# shield_v7.net
KiCad netlist of a schematic drawn in EAGLE
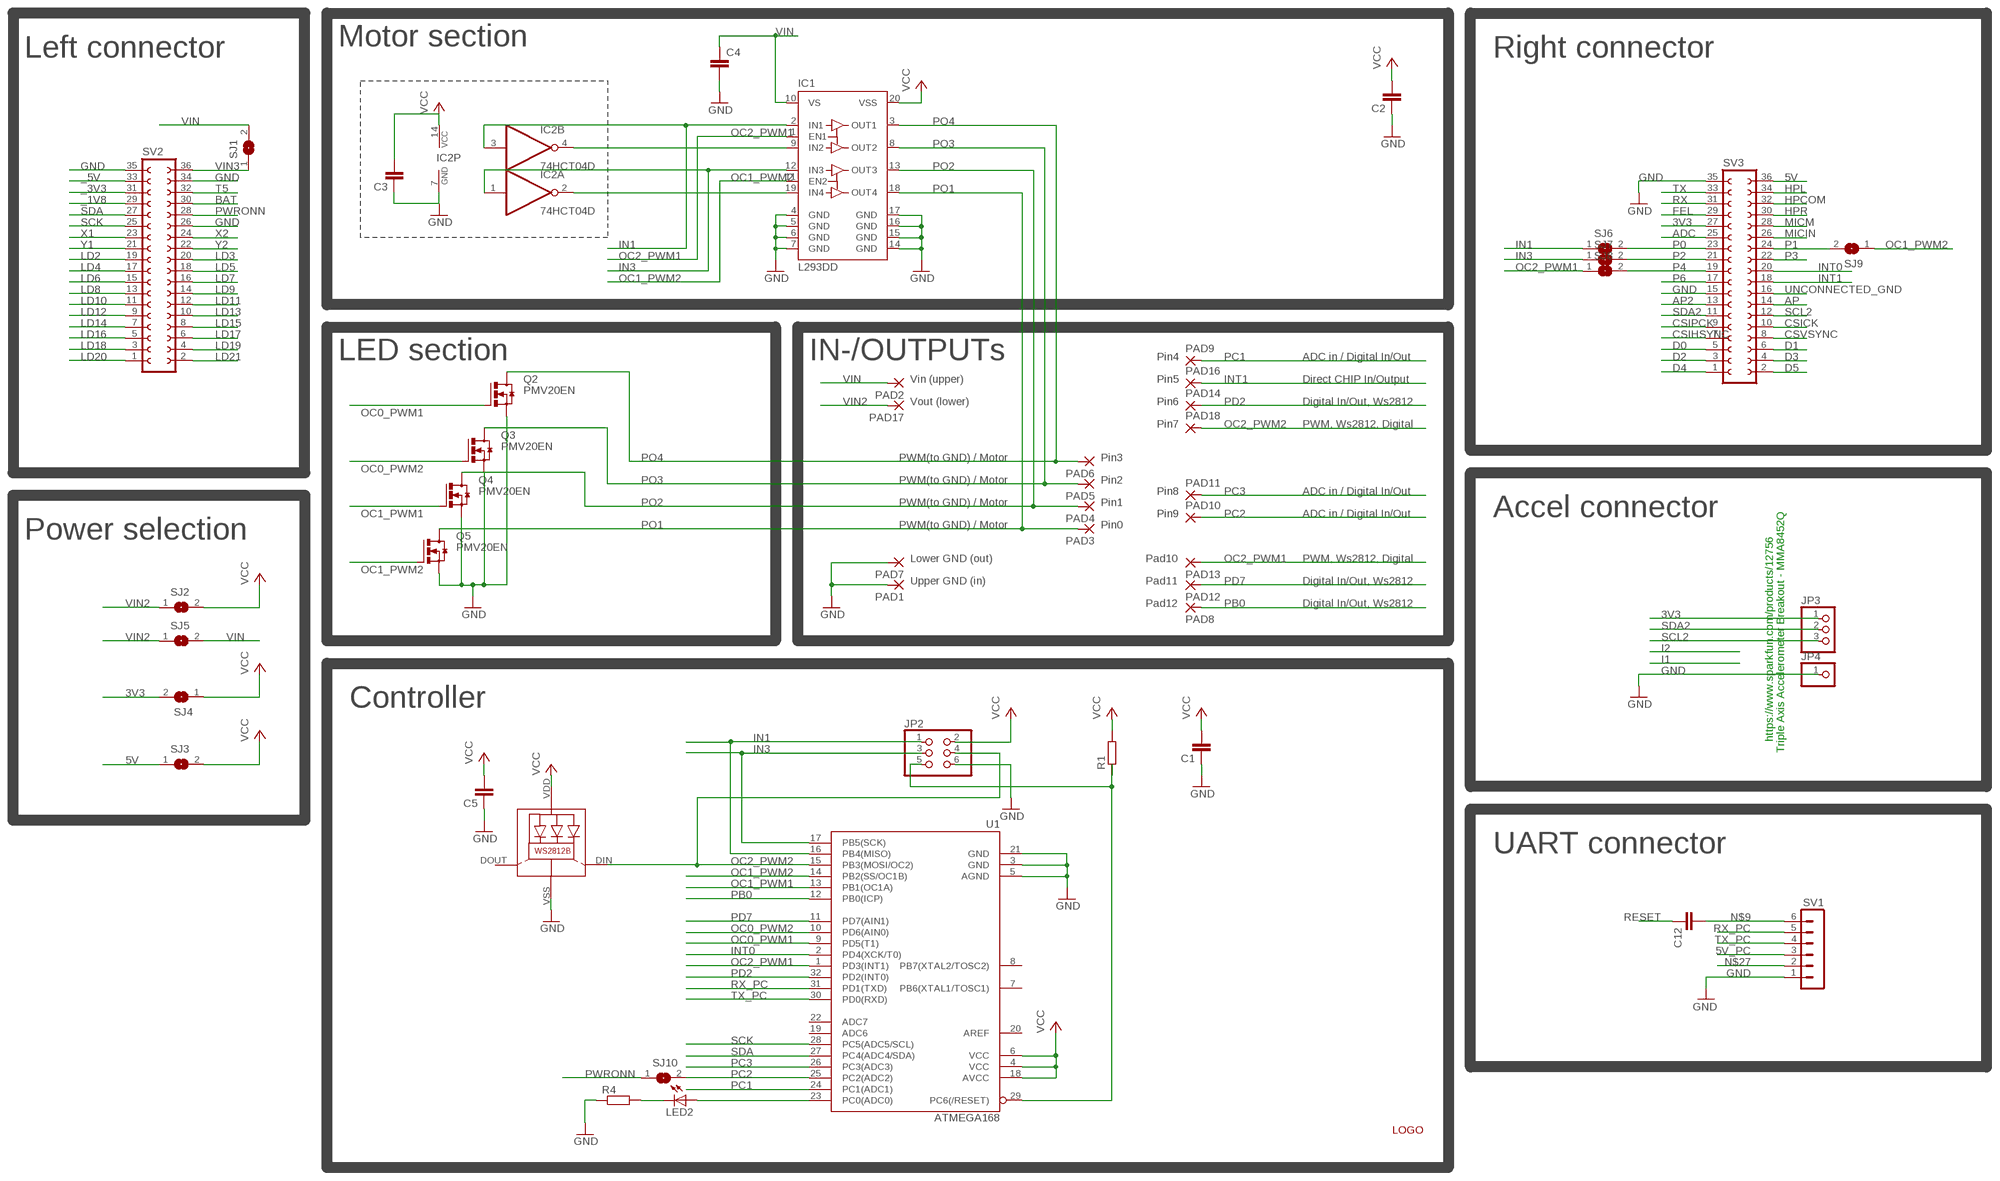
[diagram p0: schematic, sheet 1]

(export (version "E")
  (design (tool "Eeschema 10.0.6"))
  (components
    (comp (ref "C1")
      (value "C-EUC0805")
      (footprint "eagle-import:C0805")
      (libsource (lib "eagle-import") (part "C-EUC0805"))
    )
    (comp (ref "C2")
      (value "C-EUC0805")
      (footprint "eagle-import:C0805")
      (libsource (lib "eagle-import") (part "C-EUC0805"))
    )
    (comp (ref "C3")
      (value "C-EUC0805")
      (footprint "eagle-import:C0805")
      (libsource (lib "eagle-import") (part "C-EUC0805"))
    )
    (comp (ref "C4")
      (value "C-EUC1210")
      (footprint "eagle-import:C1210")
      (libsource (lib "eagle-import") (part "C-EUC1210"))
    )
    (comp (ref "C5")
      (value "C-EUC0805")
      (footprint "eagle-import:C0805")
      (libsource (lib "eagle-import") (part "C-EUC0805"))
    )
    (comp (ref "C12")
      (value "C-EUC1206")
      (footprint "eagle-import:C1206")
      (libsource (lib "eagle-import") (part "C-EUC1206"))
    )
    (comp (ref "IC1")
      (value "L293DD")
      (footprint "eagle-import:SO20")
      (libsource (lib "eagle-import") (part "L293DD"))
    )
    (comp (ref "IC2")
      (value "74HCT04D")
      (footprint "eagle-import:SO14")
      (libsource (lib "eagle-import") (part "7404DHCT"))
    )
    (comp (ref "JP2")
      (value "PINHD-2X3")
      (footprint "eagle-import:2X03")
      (libsource (lib "eagle-import") (part "PINHD-2X3"))
    )
    (comp (ref "JP3")
      (value "PINHD-1X3")
      (footprint "eagle-import:1X03")
      (libsource (lib "eagle-import") (part "PINHD-1X3"))
    )
    (comp (ref "JP4")
      (value "PINHD-1X1")
      (footprint "eagle-import:1X01")
      (libsource (lib "eagle-import") (part "PINHD-1X1"))
    )
    (comp (ref "LED1")
      (value "WS2812B")
      (footprint "eagle-import:WS2812B")
      (libsource (lib "eagle-import") (part "WS2812B"))
    )
    (comp (ref "LED2")
      (value "LEDCHIP-LED0805")
      (footprint "eagle-import:CHIP-LED0805")
      (libsource (lib "eagle-import") (part "LEDCHIP-LED0805"))
    )
    (comp (ref "PAD1")
      (value "3,17/1,3")
      (footprint "eagle-import:3,17_1,3")
      (libsource (lib "eagle-import") (part "3,17/1,3"))
    )
    (comp (ref "PAD2")
      (value "3,17/1,3")
      (footprint "eagle-import:3,17_1,3")
      (libsource (lib "eagle-import") (part "3,17/1,3"))
    )
    (comp (ref "PAD3")
      (value "3,17/1,3")
      (footprint "eagle-import:3,17_1,3")
      (libsource (lib "eagle-import") (part "3,17/1,3"))
    )
    (comp (ref "PAD4")
      (value "3,17/1,3")
      (footprint "eagle-import:3,17_1,3")
      (libsource (lib "eagle-import") (part "3,17/1,3"))
    )
    (comp (ref "PAD5")
      (value "3,17/1,3")
      (footprint "eagle-import:3,17_1,3")
      (libsource (lib "eagle-import") (part "3,17/1,3"))
    )
    (comp (ref "PAD6")
      (value "3,17/1,3")
      (footprint "eagle-import:3,17_1,3")
      (libsource (lib "eagle-import") (part "3,17/1,3"))
    )
    (comp (ref "PAD7")
      (value "3,17/1,3")
      (footprint "eagle-import:3,17_1,3")
      (libsource (lib "eagle-import") (part "3,17/1,3"))
    )
    (comp (ref "PAD8")
      (value "WIREPADSMD1,27-254")
      (footprint "eagle-import:SMD1,27-2,54")
      (libsource (lib "eagle-import") (part "WIREPADSMD1,27-254"))
    )
    (comp (ref "PAD9")
      (value "3,17/1,3")
      (footprint "eagle-import:3,17_1,3")
      (libsource (lib "eagle-import") (part "3,17/1,3"))
    )
    (comp (ref "PAD10")
      (value "3,17/1,3")
      (footprint "eagle-import:3,17_1,3")
      (libsource (lib "eagle-import") (part "3,17/1,3"))
    )
    (comp (ref "PAD11")
      (value "3,17/1,3")
      (footprint "eagle-import:3,17_1,3")
      (libsource (lib "eagle-import") (part "3,17/1,3"))
    )
    (comp (ref "PAD12")
      (value "SMD2")
      (footprint "eagle-import:SMD1,27-2,54")
      (libsource (lib "eagle-import") (part "SMD2"))
    )
    (comp (ref "PAD13")
      (value "SMD2")
      (footprint "eagle-import:SMD1,27-2,54")
      (libsource (lib "eagle-import") (part "SMD2"))
    )
    (comp (ref "PAD14")
      (value "3,17/1,3")
      (footprint "eagle-import:3,17_1,3")
      (libsource (lib "eagle-import") (part "3,17/1,3"))
    )
    (comp (ref "PAD16")
      (value "3,17/1,3")
      (footprint "eagle-import:3,17_1,3")
      (libsource (lib "eagle-import") (part "3,17/1,3"))
    )
    (comp (ref "PAD17")
      (value "3,17/1,3")
      (footprint "eagle-import:3,17_1,3")
      (libsource (lib "eagle-import") (part "3,17/1,3"))
    )
    (comp (ref "PAD18")
      (value "3,17/1,3")
      (footprint "eagle-import:3,17_1,3")
      (libsource (lib "eagle-import") (part "3,17/1,3"))
    )
    (comp (ref "Q2")
      (value "PMV20EN")
      (footprint "eagle-import:SOT223")
      (libsource (lib "eagle-import") (part "NMOSFET_SMD_223"))
    )
    (comp (ref "Q3")
      (value "PMV20EN")
      (footprint "eagle-import:SOT223")
      (libsource (lib "eagle-import") (part "NMOSFET_SMD_223"))
    )
    (comp (ref "Q4")
      (value "PMV20EN")
      (footprint "eagle-import:SOT223")
      (libsource (lib "eagle-import") (part "NMOSFET_SMD_223"))
    )
    (comp (ref "Q5")
      (value "PMV20EN")
      (footprint "eagle-import:SOT223")
      (libsource (lib "eagle-import") (part "NMOSFET_SMD_223"))
    )
    (comp (ref "R1")
      (value "R-EU_M1206")
      (footprint "eagle-import:M1206")
      (libsource (lib "eagle-import") (part "R-EU_M1206"))
    )
    (comp (ref "R4")
      (value "R-EU_M1206")
      (footprint "eagle-import:M1206")
      (libsource (lib "eagle-import") (part "R-EU_M1206"))
    )
    (comp (ref "SJ1") (value "SJ") (footprint "eagle-import:SJ") (libsource (lib "eagle-import") (part "SJ")))
    (comp (ref "SJ2") (value "SJ") (footprint "eagle-import:SJ") (libsource (lib "eagle-import") (part "SJ")))
    (comp (ref "SJ3") (value "SJ") (footprint "eagle-import:SJ") (libsource (lib "eagle-import") (part "SJ")))
    (comp (ref "SJ4") (value "SJ") (footprint "eagle-import:SJ") (libsource (lib "eagle-import") (part "SJ")))
    (comp (ref "SJ5") (value "SJ") (footprint "eagle-import:SJ") (libsource (lib "eagle-import") (part "SJ")))
    (comp (ref "SJ6") (value "SJ") (footprint "eagle-import:SJ") (libsource (lib "eagle-import") (part "SJ")))
    (comp (ref "SJ7") (value "SJ") (footprint "eagle-import:SJ") (libsource (lib "eagle-import") (part "SJ")))
    (comp (ref "SJ8") (value "SJ") (footprint "eagle-import:SJ") (libsource (lib "eagle-import") (part "SJ")))
    (comp (ref "SJ9") (value "SJ") (footprint "eagle-import:SJ") (libsource (lib "eagle-import") (part "SJ")))
    (comp (ref "SJ10")
      (value "SJ")
      (footprint "eagle-import:SJ")
      (libsource (lib "eagle-import") (part "SJ"))
    )
    (comp (ref "SV1")
      (value "MA06-1")
      (footprint "eagle-import:MA06-1")
      (libsource (lib "eagle-import") (part "MA06-1"))
    )
    (comp (ref "SV2")
      (value "FE18-2")
      (footprint "eagle-import:FE18-2")
      (libsource (lib "eagle-import") (part "FE18-2"))
    )
    (comp (ref "SV3")
      (value "FE18-2")
      (footprint "eagle-import:FE18-2")
      (libsource (lib "eagle-import") (part "FE18-2"))
    )
    (comp (ref "U$2")
      (value "LOGO")
      (footprint "eagle-import:LOGO")
      (libsource (lib "eagle-import") (part "LOGO"))
    )
    (comp (ref "U1")
      (value "ATMEGA168")
      (footprint "eagle-import:TQFP32-08")
      (libsource (lib "eagle-import") (part "ATMEGA168"))
    )
  )
  (nets
    (net (code "1") (name "/3V3") (class "Default")
      (node (ref "JP3") (pin "1") (pinfunction "1_1") (pintype "passive"))
      (node (ref "SJ4") (pin "2") (pinfunction "2_2") (pintype "passive"))
      (node (ref "SV3") (pin "27") (pinfunction "27_27") (pintype "passive"))
    )
    (net (code "2") (name "/5V") (class "Default")
      (node (ref "SJ3") (pin "1") (pinfunction "1_1") (pintype "passive"))
      (node (ref "SV3") (pin "36") (pinfunction "36_36") (pintype "passive"))
    )
    (net (code "3") (name "/5V_PC") (class "Default")
      (node (ref "SV1") (pin "3") (pinfunction "3_3") (pintype "passive"))
    )
    (net (code "4") (name "/ADC") (class "Default")
      (node (ref "SV3") (pin "25") (pinfunction "25_25") (pintype "passive"))
    )
    (net (code "5") (name "/AP") (class "Default")
      (node (ref "SV3") (pin "14") (pinfunction "14_14") (pintype "passive"))
    )
    (net (code "6") (name "/AP2") (class "Default")
      (node (ref "SV3") (pin "13") (pinfunction "13_13") (pintype "passive"))
    )
    (net (code "7") (name "/BAT") (class "Default")
      (node (ref "SV2") (pin "30") (pinfunction "30_30") (pintype "passive"))
    )
    (net (code "8") (name "/CSICK") (class "Default")
      (node (ref "SV3") (pin "10") (pinfunction "10_10") (pintype "passive"))
    )
    (net (code "9") (name "/CSIHSYNC") (class "Default")
      (node (ref "SV3") (pin "7") (pinfunction "7_7") (pintype "passive"))
    )
    (net (code "10") (name "/CSIPCK") (class "Default")
      (node (ref "SV3") (pin "9") (pinfunction "9_9") (pintype "passive"))
    )
    (net (code "11") (name "/CSVSYNC") (class "Default")
      (node (ref "SV3") (pin "8") (pinfunction "8_8") (pintype "passive"))
    )
    (net (code "12") (name "/D0") (class "Default")
      (node (ref "SV3") (pin "5") (pinfunction "5_5") (pintype "passive"))
    )
    (net (code "13") (name "/D1") (class "Default")
      (node (ref "SV3") (pin "6") (pinfunction "6_6") (pintype "passive"))
    )
    (net (code "14") (name "/D2") (class "Default")
      (node (ref "SV3") (pin "3") (pinfunction "3_3") (pintype "passive"))
    )
    (net (code "15") (name "/D3") (class "Default")
      (node (ref "SV3") (pin "4") (pinfunction "4_4") (pintype "passive"))
    )
    (net (code "16") (name "/D4") (class "Default")
      (node (ref "SV3") (pin "1") (pinfunction "1_1") (pintype "passive"))
    )
    (net (code "17") (name "/D5") (class "Default")
      (node (ref "SV3") (pin "2") (pinfunction "2_2") (pintype "passive"))
    )
    (net (code "18") (name "/FEL") (class "Default")
      (node (ref "SV3") (pin "29") (pinfunction "29_29") (pintype "passive"))
    )
    (net (code "19") (name "/HPCOM") (class "Default")
      (node (ref "SV3") (pin "32") (pinfunction "32_32") (pintype "passive"))
    )
    (net (code "20") (name "/HPL") (class "Default")
      (node (ref "SV3") (pin "34") (pinfunction "34_34") (pintype "passive"))
    )
    (net (code "21") (name "/HPR") (class "Default")
      (node (ref "SV3") (pin "30") (pinfunction "30_30") (pintype "passive"))
    )
    (net (code "24") (name "/IN1") (class "Default")
      (node (ref "IC1") (pin "2") (pinfunction "IN1_2") (pintype "input"))
      (node (ref "IC2") (pin "3") (pinfunction "I_3") (pintype "input"))
      (node (ref "JP2") (pin "1") (pinfunction "1_1") (pintype "passive"))
      (node (ref "SJ6") (pin "1") (pinfunction "1_1") (pintype "passive"))
      (node (ref "U1") (pin "16") (pinfunction "PB4(MISO)_16") (pintype "bidirectional"))
    )
    (net (code "25") (name "/IN3") (class "Default")
      (node (ref "IC1") (pin "12") (pinfunction "IN3_12") (pintype "input"))
      (node (ref "IC2") (pin "1") (pinfunction "I_1") (pintype "input"))
      (node (ref "JP2") (pin "3") (pinfunction "3_3") (pintype "passive"))
      (node (ref "SJ7") (pin "1") (pinfunction "1_1") (pintype "passive"))
      (node (ref "U1") (pin "17") (pinfunction "PB5(SCK)_17") (pintype "bidirectional"))
    )
    (net (code "26") (name "/INT0") (class "Default")
      (node (ref "SV3") (pin "20") (pinfunction "20_20") (pintype "passive"))
      (node (ref "U1") (pin "2") (pinfunction "PD4(XCK/T0)_2") (pintype "bidirectional"))
    )
    (net (code "27") (name "/INT1") (class "Default")
      (node (ref "PAD16") (pin "1") (pinfunction "P_1") (pintype "passive"))
      (node (ref "SV3") (pin "18") (pinfunction "18_18") (pintype "passive"))
    )
    (net (code "28") (name "/LD2") (class "Default")
      (node (ref "SV2") (pin "19") (pinfunction "19_19") (pintype "passive"))
    )
    (net (code "29") (name "/LD3") (class "Default")
      (node (ref "SV2") (pin "20") (pinfunction "20_20") (pintype "passive"))
    )
    (net (code "30") (name "/LD4") (class "Default")
      (node (ref "SV2") (pin "17") (pinfunction "17_17") (pintype "passive"))
    )
    (net (code "31") (name "/LD5") (class "Default")
      (node (ref "SV2") (pin "18") (pinfunction "18_18") (pintype "passive"))
    )
    (net (code "32") (name "/LD6") (class "Default")
      (node (ref "SV2") (pin "15") (pinfunction "15_15") (pintype "passive"))
    )
    (net (code "33") (name "/LD7") (class "Default")
      (node (ref "SV2") (pin "16") (pinfunction "16_16") (pintype "passive"))
    )
    (net (code "34") (name "/LD8") (class "Default")
      (node (ref "SV2") (pin "13") (pinfunction "13_13") (pintype "passive"))
    )
    (net (code "35") (name "/LD9") (class "Default")
      (node (ref "SV2") (pin "14") (pinfunction "14_14") (pintype "passive"))
    )
    (net (code "36") (name "/LD10") (class "Default")
      (node (ref "SV2") (pin "11") (pinfunction "11_11") (pintype "passive"))
    )
    (net (code "37") (name "/LD11") (class "Default")
      (node (ref "SV2") (pin "12") (pinfunction "12_12") (pintype "passive"))
    )
    (net (code "38") (name "/LD12") (class "Default")
      (node (ref "SV2") (pin "9") (pinfunction "9_9") (pintype "passive"))
    )
    (net (code "39") (name "/LD13") (class "Default")
      (node (ref "SV2") (pin "10") (pinfunction "10_10") (pintype "passive"))
    )
    (net (code "40") (name "/LD14") (class "Default")
      (node (ref "SV2") (pin "7") (pinfunction "7_7") (pintype "passive"))
    )
    (net (code "41") (name "/LD15") (class "Default")
      (node (ref "SV2") (pin "8") (pinfunction "8_8") (pintype "passive"))
    )
    (net (code "42") (name "/LD16") (class "Default")
      (node (ref "SV2") (pin "5") (pinfunction "5_5") (pintype "passive"))
    )
    (net (code "43") (name "/LD17") (class "Default")
      (node (ref "SV2") (pin "6") (pinfunction "6_6") (pintype "passive"))
    )
    (net (code "44") (name "/LD18") (class "Default")
      (node (ref "SV2") (pin "3") (pinfunction "3_3") (pintype "passive"))
    )
    (net (code "45") (name "/LD19") (class "Default")
      (node (ref "SV2") (pin "4") (pinfunction "4_4") (pintype "passive"))
    )
    (net (code "46") (name "/LD20") (class "Default")
      (node (ref "SV2") (pin "1") (pinfunction "1_1") (pintype "passive"))
    )
    (net (code "47") (name "/LD21") (class "Default")
      (node (ref "SV2") (pin "2") (pinfunction "2_2") (pintype "passive"))
    )
    (net (code "48") (name "/MICIN") (class "Default")
      (node (ref "SV3") (pin "26") (pinfunction "26_26") (pintype "passive"))
    )
    (net (code "49") (name "/MICM") (class "Default")
      (node (ref "SV3") (pin "28") (pinfunction "28_28") (pintype "passive"))
    )
    (net (code "50") (name "/N$9") (class "Default")
      (node (ref "C12") (pin "2") (pinfunction "2_2") (pintype "passive"))
      (node (ref "SV1") (pin "6") (pinfunction "6_6") (pintype "passive"))
    )
    (net (code "51") (name "/N$27") (class "Default")
      (node (ref "SV1") (pin "2") (pinfunction "2_2") (pintype "passive"))
    )
    (net (code "52") (name "/OC0_PWM1") (class "Default")
      (node (ref "Q2") (pin "1") (pinfunction "G_1") (pintype "passive"))
      (node (ref "U1") (pin "9") (pinfunction "PD5(T1)_9") (pintype "bidirectional"))
    )
    (net (code "53") (name "/OC0_PWM2") (class "Default")
      (node (ref "Q3") (pin "1") (pinfunction "G_1") (pintype "passive"))
      (node (ref "U1") (pin "10") (pinfunction "PD6(AIN0)_10") (pintype "bidirectional"))
    )
    (net (code "54") (name "/OC1_PWM1") (class "Default")
      (node (ref "Q4") (pin "1") (pinfunction "G_1") (pintype "passive"))
      (node (ref "U1") (pin "13") (pinfunction "PB1(OC1A)_13") (pintype "bidirectional"))
    )
    (net (code "55") (name "/OC1_PWM2") (class "Default")
      (node (ref "IC1") (pin "11") (pinfunction "EN2_11") (pintype "input"))
      (node (ref "Q5") (pin "1") (pinfunction "G_1") (pintype "passive"))
      (node (ref "SJ9") (pin "1") (pinfunction "1_1") (pintype "passive"))
      (node (ref "U1") (pin "14") (pinfunction "PB2(SS/OC1B)_14") (pintype "bidirectional"))
    )
    (net (code "56") (name "/OC2_PWM1") (class "Default")
      (node (ref "IC1") (pin "1") (pinfunction "EN1_1") (pintype "input"))
      (node (ref "PAD13") (pin "1") (pinfunction "P_1") (pintype "passive"))
      (node (ref "SJ8") (pin "1") (pinfunction "1_1") (pintype "passive"))
      (node (ref "U1") (pin "1") (pinfunction "PD3(INT1)_1") (pintype "bidirectional"))
    )
    (net (code "57") (name "/OC2_PWM2") (class "Default")
      (node (ref "JP2") (pin "4") (pinfunction "4_4") (pintype "passive"))
      (node (ref "LED1") (pin "DIN") (pinfunction "DI_DIN") (pintype "input"))
      (node (ref "PAD18") (pin "1") (pinfunction "P_1") (pintype "passive"))
      (node (ref "U1") (pin "15") (pinfunction "PB3(MOSI/OC2)_15") (pintype "bidirectional"))
    )
    (net (code "58") (name "/P0") (class "Default")
      (node (ref "SJ6") (pin "2") (pinfunction "2_2") (pintype "passive"))
      (node (ref "SV3") (pin "23") (pinfunction "23_23") (pintype "passive"))
    )
    (net (code "59") (name "/P1") (class "Default")
      (node (ref "SJ9") (pin "2") (pinfunction "2_2") (pintype "passive"))
      (node (ref "SV3") (pin "24") (pinfunction "24_24") (pintype "passive"))
    )
    (net (code "60") (name "/P2") (class "Default")
      (node (ref "SJ7") (pin "2") (pinfunction "2_2") (pintype "passive"))
      (node (ref "SV3") (pin "21") (pinfunction "21_21") (pintype "passive"))
    )
    (net (code "61") (name "/P3") (class "Default")
      (node (ref "SV3") (pin "22") (pinfunction "22_22") (pintype "passive"))
    )
    (net (code "62") (name "/P4") (class "Default")
      (node (ref "SJ8") (pin "2") (pinfunction "2_2") (pintype "passive"))
      (node (ref "SV3") (pin "19") (pinfunction "19_19") (pintype "passive"))
    )
    (net (code "63") (name "/P6") (class "Default")
      (node (ref "SV3") (pin "17") (pinfunction "17_17") (pintype "passive"))
    )
    (net (code "64") (name "/PB0") (class "Default")
      (node (ref "PAD8") (pin "1") (pinfunction "P_1") (pintype "passive"))
      (node (ref "U1") (pin "12") (pinfunction "PB0(ICP)_12") (pintype "bidirectional"))
    )
    (net (code "65") (name "/PC1") (class "Default")
      (node (ref "PAD9") (pin "1") (pinfunction "P_1") (pintype "passive"))
      (node (ref "U1") (pin "24") (pinfunction "PC1(ADC1)_24") (pintype "bidirectional"))
    )
    (net (code "66") (name "/PC2") (class "Default")
      (node (ref "PAD10") (pin "1") (pinfunction "P_1") (pintype "passive"))
      (node (ref "SJ10") (pin "2") (pinfunction "2_2") (pintype "passive"))
      (node (ref "U1") (pin "25") (pinfunction "PC2(ADC2)_25") (pintype "bidirectional"))
    )
    (net (code "67") (name "/PC3") (class "Default")
      (node (ref "PAD11") (pin "1") (pinfunction "P_1") (pintype "passive"))
      (node (ref "U1") (pin "26") (pinfunction "PC3(ADC3)_26") (pintype "bidirectional"))
    )
    (net (code "68") (name "/PD2") (class "Default")
      (node (ref "PAD14") (pin "1") (pinfunction "P_1") (pintype "passive"))
      (node (ref "U1") (pin "32") (pinfunction "PD2(INT0)_32") (pintype "bidirectional"))
    )
    (net (code "69") (name "/PD7") (class "Default")
      (node (ref "PAD12") (pin "1") (pinfunction "P_1") (pintype "passive"))
      (node (ref "U1") (pin "11") (pinfunction "PD7(AIN1)_11") (pintype "bidirectional"))
    )
    (net (code "70") (name "/PO1") (class "Default")
      (node (ref "IC1") (pin "18") (pinfunction "OUT4_18") (pintype "output"))
      (node (ref "PAD3") (pin "1") (pinfunction "P_1") (pintype "passive"))
      (node (ref "Q5") (pin "2") (pinfunction "D_2") (pintype "passive"))
      (node (ref "Q5") (pin "4") (pinfunction "D_4") (pintype "passive"))
    )
    (net (code "71") (name "/PO2") (class "Default")
      (node (ref "IC1") (pin "13") (pinfunction "OUT3_13") (pintype "output"))
      (node (ref "PAD4") (pin "1") (pinfunction "P_1") (pintype "passive"))
      (node (ref "Q4") (pin "2") (pinfunction "D_2") (pintype "passive"))
      (node (ref "Q4") (pin "4") (pinfunction "D_4") (pintype "passive"))
    )
    (net (code "72") (name "/PO3") (class "Default")
      (node (ref "IC1") (pin "8") (pinfunction "OUT2_8") (pintype "output"))
      (node (ref "PAD5") (pin "1") (pinfunction "P_1") (pintype "passive"))
      (node (ref "Q3") (pin "2") (pinfunction "D_2") (pintype "passive"))
      (node (ref "Q3") (pin "4") (pinfunction "D_4") (pintype "passive"))
    )
    (net (code "73") (name "/PO4") (class "Default")
      (node (ref "IC1") (pin "3") (pinfunction "OUT1_3") (pintype "output"))
      (node (ref "PAD6") (pin "1") (pinfunction "P_1") (pintype "passive"))
      (node (ref "Q2") (pin "2") (pinfunction "D_2") (pintype "passive"))
      (node (ref "Q2") (pin "4") (pinfunction "D_4") (pintype "passive"))
    )
    (net (code "74") (name "/PWRONN") (class "Default")
      (node (ref "SJ10") (pin "1") (pinfunction "1_1") (pintype "passive"))
      (node (ref "SV2") (pin "28") (pinfunction "28_28") (pintype "passive"))
    )
    (net (code "75") (name "/RESET") (class "Default")
      (node (ref "C12") (pin "1") (pinfunction "1_1") (pintype "passive"))
      (node (ref "JP2") (pin "5") (pinfunction "5_5") (pintype "passive"))
      (node (ref "R1") (pin "1") (pinfunction "1_1") (pintype "passive"))
      (node (ref "U1") (pin "29") (pinfunction "PC6(/RESET)_29") (pintype "bidirectional"))
    )
    (net (code "76") (name "/RX") (class "Default")
      (node (ref "SV3") (pin "31") (pinfunction "31_31") (pintype "passive"))
    )
    (net (code "77") (name "/RX_PC") (class "Default")
      (node (ref "SV1") (pin "5") (pinfunction "5_5") (pintype "passive"))
      (node (ref "U1") (pin "31") (pinfunction "PD1(TXD)_31") (pintype "bidirectional"))
    )
    (net (code "78") (name "/SCK") (class "Default")
      (node (ref "SV2") (pin "25") (pinfunction "25_25") (pintype "passive"))
      (node (ref "U1") (pin "28") (pinfunction "PC5(ADC5/SCL)_28") (pintype "bidirectional"))
    )
    (net (code "79") (name "/SCL2") (class "Default")
      (node (ref "JP3") (pin "3") (pinfunction "3_3") (pintype "passive"))
      (node (ref "SV3") (pin "12") (pinfunction "12_12") (pintype "passive"))
    )
    (net (code "80") (name "/SDA") (class "Default")
      (node (ref "SV2") (pin "27") (pinfunction "27_27") (pintype "passive"))
      (node (ref "U1") (pin "27") (pinfunction "PC4(ADC4/SDA)_27") (pintype "bidirectional"))
    )
    (net (code "81") (name "/SDA2") (class "Default")
      (node (ref "JP3") (pin "2") (pinfunction "2_2") (pintype "passive"))
      (node (ref "SV3") (pin "11") (pinfunction "11_11") (pintype "passive"))
    )
    (net (code "82") (name "/T5") (class "Default")
      (node (ref "SV2") (pin "32") (pinfunction "32_32") (pintype "passive"))
    )
    (net (code "83") (name "/TX") (class "Default")
      (node (ref "SV3") (pin "33") (pinfunction "33_33") (pintype "passive"))
    )
    (net (code "84") (name "/TX_PC") (class "Default")
      (node (ref "SV1") (pin "4") (pinfunction "4_4") (pintype "passive"))
      (node (ref "U1") (pin "30") (pinfunction "PD0(RXD)_30") (pintype "bidirectional"))
    )
    (net (code "85") (name "/UNCONNECTED_GND") (class "Default")
      (node (ref "SV3") (pin "16") (pinfunction "16_16") (pintype "passive"))
    )
    (net (code "86") (name "/VIN") (class "Default")
      (node (ref "C4") (pin "1") (pinfunction "1_1") (pintype "passive"))
      (node (ref "IC1") (pin "10") (pinfunction "VS_10") (pintype "power_in"))
      (node (ref "PAD2") (pin "1") (pinfunction "P_1") (pintype "passive"))
      (node (ref "SJ1") (pin "2") (pinfunction "2_2") (pintype "passive"))
      (node (ref "SJ5") (pin "2") (pinfunction "2_2") (pintype "passive"))
    )
    (net (code "87") (name "/VIN2") (class "Default")
      (node (ref "PAD17") (pin "1") (pinfunction "P_1") (pintype "passive"))
      (node (ref "SJ2") (pin "1") (pinfunction "1_1") (pintype "passive"))
      (node (ref "SJ5") (pin "1") (pinfunction "1_1") (pintype "passive"))
    )
    (net (code "88") (name "/VIN3") (class "Default")
      (node (ref "SJ1") (pin "1") (pinfunction "1_1") (pintype "passive"))
      (node (ref "SV2") (pin "36") (pinfunction "36_36") (pintype "passive"))
    )
    (net (code "89") (name "/X1") (class "Default")
      (node (ref "SV2") (pin "23") (pinfunction "23_23") (pintype "passive"))
    )
    (net (code "90") (name "/X2") (class "Default")
      (node (ref "SV2") (pin "24") (pinfunction "24_24") (pintype "passive"))
    )
    (net (code "91") (name "/Y1") (class "Default")
      (node (ref "SV2") (pin "21") (pinfunction "21_21") (pintype "passive"))
    )
    (net (code "92") (name "/Y2") (class "Default")
      (node (ref "SV2") (pin "22") (pinfunction "22_22") (pintype "passive"))
    )
    (net (code "93") (name "/_1V8") (class "Default")
      (node (ref "SV2") (pin "29") (pinfunction "29_29") (pintype "passive"))
    )
    (net (code "94") (name "/_3V3") (class "Default")
      (node (ref "SV2") (pin "31") (pinfunction "31_31") (pintype "passive"))
    )
    (net (code "95") (name "/_5V") (class "Default")
      (node (ref "SV2") (pin "33") (pinfunction "33_33") (pintype "passive"))
    )
    (net (code "96") (name "GND") (class "Default")
      (node (ref "C1") (pin "1") (pinfunction "1_1") (pintype "passive"))
      (node (ref "C2") (pin "1") (pinfunction "1_1") (pintype "passive"))
      (node (ref "C3") (pin "1") (pinfunction "1_1") (pintype "passive"))
      (node (ref "C4") (pin "2") (pinfunction "2_2") (pintype "passive"))
      (node (ref "C5") (pin "1") (pinfunction "1_1") (pintype "passive"))
      (node (ref "IC1") (pin "14") (pinfunction "GND_14") (pintype "power_in"))
      (node (ref "IC1") (pin "15") (pinfunction "GND_15") (pintype "power_in"))
      (node (ref "IC1") (pin "16") (pinfunction "GND_16") (pintype "power_in"))
      (node (ref "IC1") (pin "17") (pinfunction "GND_17") (pintype "power_in"))
      (node (ref "IC1") (pin "4") (pinfunction "GND_4") (pintype "power_in"))
      (node (ref "IC1") (pin "5") (pinfunction "GND_5") (pintype "power_in"))
      (node (ref "IC1") (pin "6") (pinfunction "GND_6") (pintype "power_in"))
      (node (ref "IC1") (pin "7") (pinfunction "GND_7") (pintype "power_in"))
      (node (ref "IC2") (pin "7") (pinfunction "GND_7") (pintype "power_in"))
      (node (ref "JP2") (pin "6") (pinfunction "6_6") (pintype "passive"))
      (node (ref "JP4") (pin "1") (pinfunction "1_1") (pintype "passive"))
      (node (ref "LED1") (pin "VSS") (pinfunction "GND_VSS") (pintype "power_in"))
      (node (ref "PAD1") (pin "1") (pinfunction "P_1") (pintype "passive"))
      (node (ref "PAD7") (pin "1") (pinfunction "P_1") (pintype "passive"))
      (node (ref "Q2") (pin "3") (pinfunction "S_3") (pintype "passive"))
      (node (ref "Q3") (pin "3") (pinfunction "S_3") (pintype "passive"))
      (node (ref "Q4") (pin "3") (pinfunction "S_3") (pintype "passive"))
      (node (ref "Q5") (pin "3") (pinfunction "S_3") (pintype "passive"))
      (node (ref "R4") (pin "1") (pinfunction "1_1") (pintype "passive"))
      (node (ref "SV1") (pin "1") (pinfunction "1_1") (pintype "passive"))
      (node (ref "SV2") (pin "26") (pinfunction "26_26") (pintype "passive"))
      (node (ref "SV2") (pin "34") (pinfunction "34_34") (pintype "passive"))
      (node (ref "SV2") (pin "35") (pinfunction "35_35") (pintype "passive"))
      (node (ref "SV3") (pin "15") (pinfunction "15_15") (pintype "passive"))
      (node (ref "SV3") (pin "35") (pinfunction "35_35") (pintype "passive"))
      (node (ref "U1") (pin "21") (pinfunction "GND_21") (pintype "bidirectional"))
      (node (ref "U1") (pin "3") (pinfunction "GND_3") (pintype "bidirectional"))
      (node (ref "U1") (pin "5") (pinfunction "AGND_5") (pintype "bidirectional"))
    )
    (net (code "97") (name "Net-(IC1-IN2)") (class "Default")
      (node (ref "IC1") (pin "9") (pinfunction "IN2_9") (pintype "input"))
      (node (ref "IC2") (pin "4") (pinfunction "O_4") (pintype "output"))
    )
    (net (code "98") (name "Net-(IC1-IN4)") (class "Default")
      (node (ref "IC1") (pin "19") (pinfunction "IN4_19") (pintype "input"))
      (node (ref "IC2") (pin "2") (pinfunction "O_2") (pintype "output"))
    )
    (net (code "99") (name "Net-(LED2-PadC)") (class "Default")
      (node (ref "LED2") (pin "C") (pinfunction "C_C") (pintype "passive"))
      (node (ref "R4") (pin "2") (pinfunction "2_2") (pintype "passive"))
    )
    (net (code "100") (name "Net-(U1-PC0(ADC0))") (class "Default")
      (node (ref "LED2") (pin "A") (pinfunction "A_A") (pintype "passive"))
      (node (ref "U1") (pin "23") (pinfunction "PC0(ADC0)_23") (pintype "bidirectional"))
    )
    (net (code "101") (name "VCC") (class "Default")
      (node (ref "C1") (pin "2") (pinfunction "2_2") (pintype "passive"))
      (node (ref "C2") (pin "2") (pinfunction "2_2") (pintype "passive"))
      (node (ref "C3") (pin "2") (pinfunction "2_2") (pintype "passive"))
      (node (ref "C5") (pin "2") (pinfunction "2_2") (pintype "passive"))
      (node (ref "IC1") (pin "20") (pinfunction "VSS_20") (pintype "power_in"))
      (node (ref "IC2") (pin "14") (pinfunction "VCC_14") (pintype "power_in"))
      (node (ref "JP2") (pin "2") (pinfunction "2_2") (pintype "passive"))
      (node (ref "LED1") (pin "VDD") (pinfunction "VDD_VDD") (pintype "power_in"))
      (node (ref "R1") (pin "2") (pinfunction "2_2") (pintype "passive"))
      (node (ref "SJ2") (pin "2") (pinfunction "2_2") (pintype "passive"))
      (node (ref "SJ3") (pin "2") (pinfunction "2_2") (pintype "passive"))
      (node (ref "SJ4") (pin "1") (pinfunction "1_1") (pintype "passive"))
      (node (ref "U1") (pin "18") (pinfunction "AVCC_18") (pintype "bidirectional"))
      (node (ref "U1") (pin "4") (pinfunction "VCC_4") (pintype "bidirectional"))
      (node (ref "U1") (pin "6") (pinfunction "VCC_6") (pintype "bidirectional"))
    )
    (net (code "102") (name "unconnected-(LED1-DO-PadDOUT)") (class "Default")
      (node (ref "LED1") (pin "DOUT") (pinfunction "DO_DOUT") (pintype "output"))
    )
    (net (code "103") (name "unconnected-(U1-ADC6-Pad19)") (class "Default")
      (node (ref "U1") (pin "19") (pinfunction "ADC6_19") (pintype "bidirectional"))
    )
    (net (code "104") (name "unconnected-(U1-ADC7-Pad22)") (class "Default")
      (node (ref "U1") (pin "22") (pinfunction "ADC7_22") (pintype "bidirectional"))
    )
    (net (code "105") (name "unconnected-(U1-AREF-Pad20)") (class "Default")
      (node (ref "U1") (pin "20") (pinfunction "AREF_20") (pintype "bidirectional"))
    )
    (net (code "106") (name "unconnected-(U1-PB6(XTAL1{slash}TOSC1)-Pad7)") (class "Default")
      (node (ref "U1") (pin "7") (pinfunction "PB6(XTAL1/TOSC1)_7") (pintype "bidirectional"))
    )
    (net (code "107") (name "unconnected-(U1-PB7(XTAL2{slash}TOSC2)-Pad8)") (class "Default")
      (node (ref "U1") (pin "8") (pinfunction "PB7(XTAL2/TOSC2)_8") (pintype "bidirectional"))
    )
  )
)
